# PCB_Invernadero.net
KiCad netlist of a schematic drawn in Altium Designer
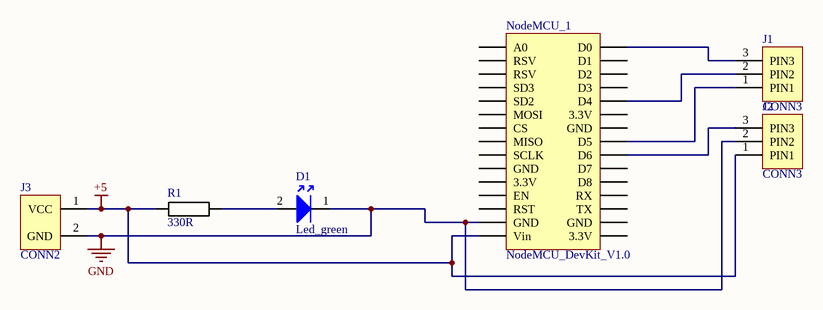
[diagram p0: PCB_Invernadero.SchDoc]

(export (version "E")
  (design (tool "Eeschema 10.0.6"))
  (components
    (comp (ref "D1")
      (value "Led_green")
      (footprint "Diode_5mm_green")
      (libsource (lib "Schlib-PCB-Invernadero") (part "Led_green"))
    )
    (comp (ref "J1")
      (value "CONN3")
      (footprint "CONN3")
      (libsource (lib "Schlib-PCB-Invernadero") (part "Bornera_3_pin"))
    )
    (comp (ref "J2")
      (value "CONN3")
      (footprint "CONN3")
      (libsource (lib "Schlib-PCB-Invernadero") (part "Bornera_3_pin"))
    )
    (comp (ref "J3")
      (value "CONN2")
      (footprint "CONN2")
      (libsource (lib "Schlib-PCB-Invernadero") (part "Conector"))
    )
    (comp (ref "NodeMCU_1")
      (value "NodeMCU_DevKit_V1.0")
      (footprint "NodeMCU_DevKit_V1.0")
      (libsource (lib "Schlib-PCB-Invernadero") (part "NodeMCU"))
    )
    (comp (ref "R1")
      (value "330R")
      (footprint "330R_P8mm_0.25W")
      (libsource (lib "Schlib-PCB-Invernadero") (part "330R_0.25W"))
    )
  )
  (nets
    (net (code "1") (name "+5") (class "Default")
      (node (ref "J2") (pin "1") (pinfunction "PIN1_1") (pintype "passive"))
      (node (ref "J3") (pin "1") (pinfunction "VCC_1") (pintype "passive"))
      (node (ref "NodeMCU_1") (pin "Vin") (pinfunction "Vin_Vin") (pintype "passive"))
      (node (ref "R1") (pin "1") (pinfunction "1_1") (pintype "passive"))
    )
    (net (code "2") (name "GND") (class "Default")
      (node (ref "D1") (pin "1") (pinfunction "1_1") (pintype "passive"))
      (node (ref "J2") (pin "2") (pinfunction "PIN2_2") (pintype "passive"))
      (node (ref "J3") (pin "2") (pinfunction "GND_2") (pintype "passive"))
      (node (ref "NodeMCU_1") (pin "GND") (pinfunction "GND_GND") (pintype "passive"))
    )
    (net (code "3") (name "Net-(D1-Pad2)") (class "Default")
      (node (ref "D1") (pin "2") (pinfunction "2_2") (pintype "passive"))
      (node (ref "R1") (pin "2") (pinfunction "2_2") (pintype "passive"))
    )
    (net (code "4") (name "Net-(J1-PIN1)") (class "Default")
      (node (ref "J1") (pin "1") (pinfunction "PIN1_1") (pintype "passive"))
      (node (ref "NodeMCU_1") (pin "D5") (pinfunction "D5_D5") (pintype "passive"))
    )
    (net (code "5") (name "Net-(J1-PIN2)") (class "Default")
      (node (ref "J1") (pin "2") (pinfunction "PIN2_2") (pintype "passive"))
      (node (ref "NodeMCU_1") (pin "D4") (pinfunction "D4_D4") (pintype "passive"))
    )
    (net (code "6") (name "Net-(J1-PIN3)") (class "Default")
      (node (ref "J1") (pin "3") (pinfunction "PIN3_3") (pintype "passive"))
      (node (ref "NodeMCU_1") (pin "D0") (pinfunction "D0_D0") (pintype "passive"))
    )
    (net (code "7") (name "Net-(J2-PIN3)") (class "Default")
      (node (ref "J2") (pin "3") (pinfunction "PIN3_3") (pintype "passive"))
      (node (ref "NodeMCU_1") (pin "D6") (pinfunction "D6_D6") (pintype "passive"))
    )
    (net (code "8") (name "unconnected-(NodeMCU_1-Pad3.3V)") (class "Default")
      (node (ref "NodeMCU_1") (pin "3.3V") (pinfunction "3.3V_3.3V") (pintype "passive"))
    )
    (net (code "9") (name "unconnected-(NodeMCU_1-Pad3.3V)_1") (class "Default")
      (node (ref "NodeMCU_1") (pin "3.3V") (pinfunction "3.3V_3.3V") (pintype "passive"))
    )
    (net (code "10") (name "unconnected-(NodeMCU_1-Pad3.3V)_2") (class "Default")
      (node (ref "NodeMCU_1") (pin "3.3V") (pinfunction "3.3V_3.3V") (pintype "passive"))
    )
    (net (code "11") (name "unconnected-(NodeMCU_1-PadA0)") (class "Default")
      (node (ref "NodeMCU_1") (pin "A0") (pinfunction "A0_A0") (pintype "passive"))
    )
    (net (code "12") (name "unconnected-(NodeMCU_1-PadCS)") (class "Default")
      (node (ref "NodeMCU_1") (pin "CS") (pinfunction "CS_CS") (pintype "passive"))
    )
    (net (code "13") (name "unconnected-(NodeMCU_1-PadD1)") (class "Default")
      (node (ref "NodeMCU_1") (pin "D1") (pinfunction "D1_D1") (pintype "passive"))
    )
    (net (code "14") (name "unconnected-(NodeMCU_1-PadD2)") (class "Default")
      (node (ref "NodeMCU_1") (pin "D2") (pinfunction "D2_D2") (pintype "passive"))
    )
    (net (code "15") (name "unconnected-(NodeMCU_1-PadD3)") (class "Default")
      (node (ref "NodeMCU_1") (pin "D3") (pinfunction "D3_D3") (pintype "passive"))
    )
    (net (code "16") (name "unconnected-(NodeMCU_1-PadD7)") (class "Default")
      (node (ref "NodeMCU_1") (pin "D7") (pinfunction "D7_D7") (pintype "passive"))
    )
    (net (code "17") (name "unconnected-(NodeMCU_1-PadD8)") (class "Default")
      (node (ref "NodeMCU_1") (pin "D8") (pinfunction "D8_D8") (pintype "passive"))
    )
    (net (code "18") (name "unconnected-(NodeMCU_1-PadEN)") (class "Default")
      (node (ref "NodeMCU_1") (pin "EN") (pinfunction "EN_EN") (pintype "passive"))
    )
    (net (code "19") (name "unconnected-(NodeMCU_1-PadGND)") (class "Default")
      (node (ref "NodeMCU_1") (pin "GND") (pinfunction "GND_GND") (pintype "passive"))
    )
    (net (code "20") (name "unconnected-(NodeMCU_1-PadGND)_1") (class "Default")
      (node (ref "NodeMCU_1") (pin "GND") (pinfunction "GND_GND") (pintype "passive"))
    )
    (net (code "21") (name "unconnected-(NodeMCU_1-PadGND)_2") (class "Default")
      (node (ref "NodeMCU_1") (pin "GND") (pinfunction "GND_GND") (pintype "passive"))
    )
    (net (code "22") (name "unconnected-(NodeMCU_1-PadMISO)") (class "Default")
      (node (ref "NodeMCU_1") (pin "MISO") (pinfunction "MISO_MISO") (pintype "passive"))
    )
    (net (code "23") (name "unconnected-(NodeMCU_1-PadMOSI)") (class "Default")
      (node (ref "NodeMCU_1") (pin "MOSI") (pinfunction "MOSI_MOSI") (pintype "passive"))
    )
    (net (code "24") (name "unconnected-(NodeMCU_1-PadRST)") (class "Default")
      (node (ref "NodeMCU_1") (pin "RST") (pinfunction "RST_RST") (pintype "passive"))
    )
    (net (code "25") (name "unconnected-(NodeMCU_1-PadRSV)") (class "Default")
      (node (ref "NodeMCU_1") (pin "RSV") (pinfunction "RSV_RSV") (pintype "passive"))
    )
    (net (code "26") (name "unconnected-(NodeMCU_1-PadRSV)_1") (class "Default")
      (node (ref "NodeMCU_1") (pin "RSV") (pinfunction "RSV_RSV") (pintype "passive"))
    )
    (net (code "27") (name "unconnected-(NodeMCU_1-PadRX)") (class "Default")
      (node (ref "NodeMCU_1") (pin "RX") (pinfunction "RX_RX") (pintype "passive"))
    )
    (net (code "28") (name "unconnected-(NodeMCU_1-PadSCLK)") (class "Default")
      (node (ref "NodeMCU_1") (pin "SCLK") (pinfunction "SCLK_SCLK") (pintype "passive"))
    )
    (net (code "29") (name "unconnected-(NodeMCU_1-PadSD2)") (class "Default")
      (node (ref "NodeMCU_1") (pin "SD2") (pinfunction "SD2_SD2") (pintype "passive"))
    )
    (net (code "30") (name "unconnected-(NodeMCU_1-PadSD3)") (class "Default")
      (node (ref "NodeMCU_1") (pin "SD3") (pinfunction "SD3_SD3") (pintype "passive"))
    )
    (net (code "31") (name "unconnected-(NodeMCU_1-PadTX)") (class "Default")
      (node (ref "NodeMCU_1") (pin "TX") (pinfunction "TX_TX") (pintype "passive"))
    )
  )
)
